# 02-MCU.net
KiCad netlist of a schematic drawn in Altium Designer
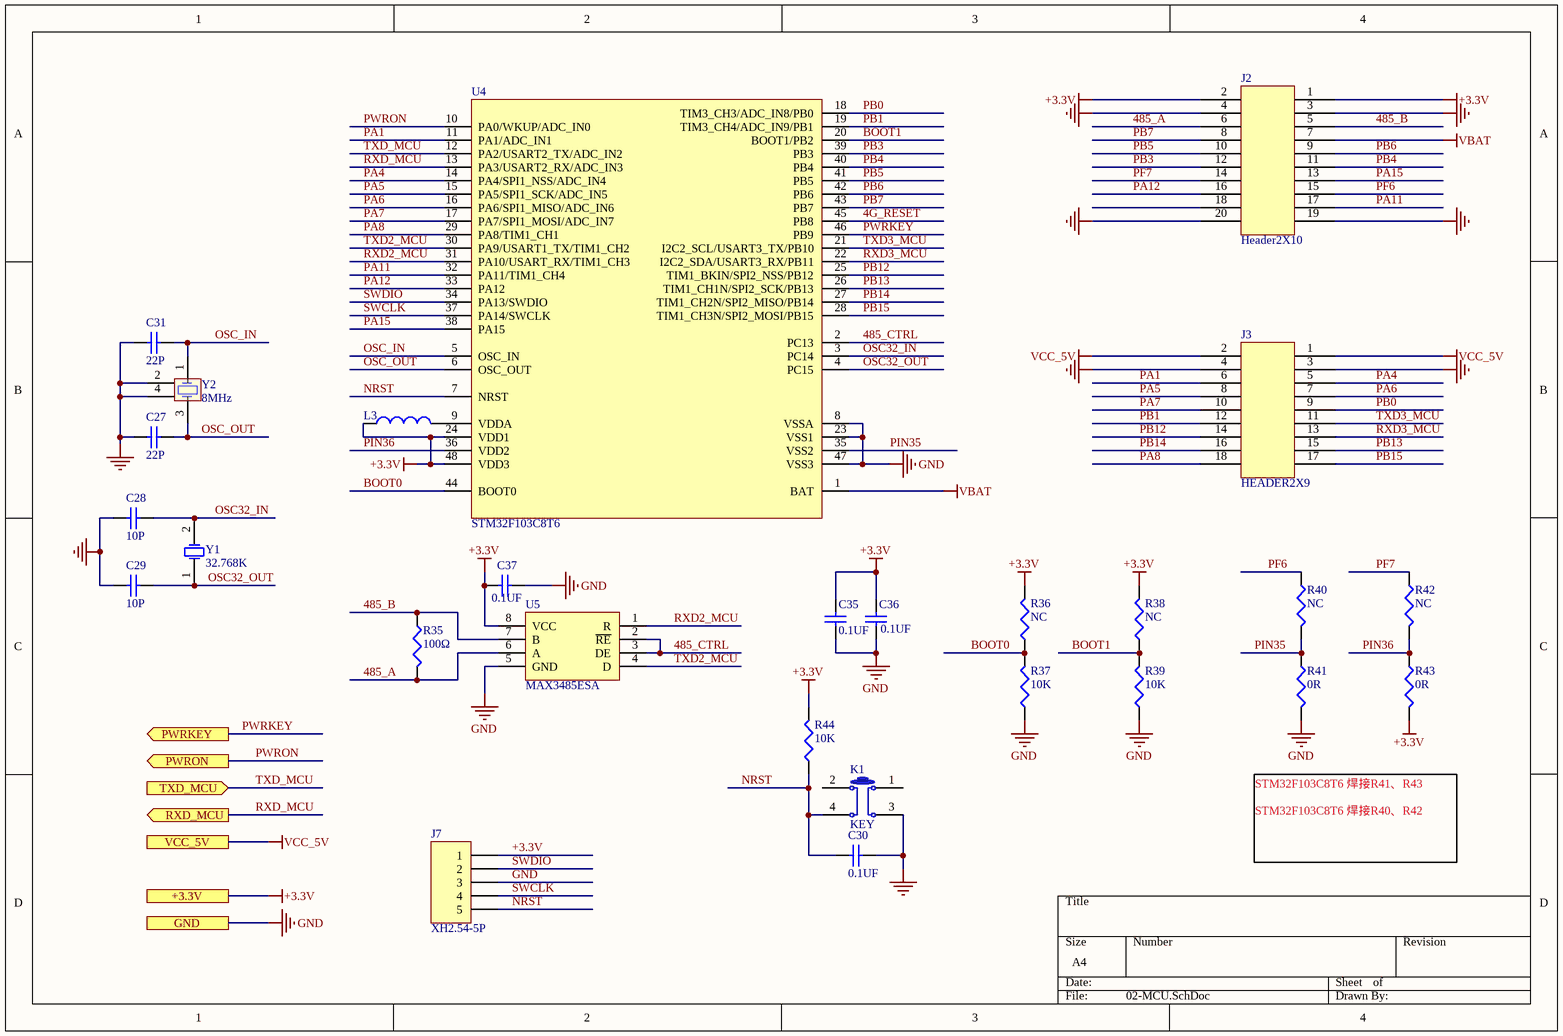
[diagram p0: 02-MCU.SchDoc]

(export (version "E")
  (design (tool "Eeschema 10.0.6"))
  (components
    (comp (ref "C27")
      (value "22P")
      (footprint "0603_C")
      (description "Capacitor")
      (fields (field (name "Comment") "Cap") (field (name "PUBLISHER") "Altium Limited"))
      (libsource (lib "Miscellaneous Devices") (part "Cap"))
    )
    (comp (ref "C28")
      (value "10P")
      (footprint "0603_C")
      (description "Capacitor")
      (fields (field (name "Comment") "Cap") (field (name "PUBLISHER") "Altium Limited"))
      (libsource (lib "Miscellaneous Devices") (part "Cap"))
    )
    (comp (ref "C29")
      (value "10P")
      (footprint "0603_C")
      (description "Capacitor")
      (fields (field (name "Comment") "Cap") (field (name "PUBLISHER") "Altium Limited"))
      (libsource (lib "Miscellaneous Devices") (part "Cap"))
    )
    (comp (ref "C30")
      (value "0.1UF")
      (footprint "0603_C")
      (description "Capacitor")
      (fields (field (name "Comment") "Cap") (field (name "PUBLISHER") "Altium Limited"))
      (libsource (lib "Miscellaneous Devices") (part "Cap"))
    )
    (comp (ref "C31")
      (value "22P")
      (footprint "0603_C")
      (description "Capacitor")
      (fields (field (name "Comment") "Cap") (field (name "PUBLISHER") "Altium Limited"))
      (libsource (lib "Miscellaneous Devices") (part "Cap"))
    )
    (comp (ref "C35")
      (value "0.1UF")
      (footprint "0603_C")
      (description "Capacitor")
      (fields (field (name "Comment") "Cap") (field (name "PUBLISHER") "Altium Limited"))
      (libsource (lib "Miscellaneous Devices") (part "Cap"))
    )
    (comp (ref "C36")
      (value "0.1UF")
      (footprint "0603_C")
      (description "Capacitor")
      (fields (field (name "Comment") "Cap") (field (name "PUBLISHER") "Altium Limited"))
      (libsource (lib "Miscellaneous Devices") (part "Cap"))
    )
    (comp (ref "C37")
      (value "0.1UF")
      (footprint "0603_C")
      (description "Capacitor")
      (fields (field (name "Comment") "Cap") (field (name "PUBLISHER") "Altium Limited"))
      (libsource (lib "Miscellaneous Devices") (part "Cap"))
    )
    (comp (ref "J2")
      (value "Header2X10")
      (footprint "DIP20-2.54-2.54")
      (libsource (lib "MySchlib") (part "Header2X10"))
    )
    (comp (ref "J3")
      (value "HEADER2X9")
      (footprint "DIP18-2.54-2.54")
      (libsource (lib "MySchlib") (part "HEADER2X9"))
    )
    (comp (ref "J7")
      (value "XH2.54-5P")
      (footprint "SIP5")
      (description "Header, 5-Pin, Right Angle")
      (fields (field (name "PUBLISHER") "Altium Limited"))
      (libsource (lib "Miscellaneous Connectors") (part "Header 5H"))
    )
    (comp (ref "K1") (value "KEY") (footprint "KEY_SMD5465") (libsource (lib "Schlib1") (part "KEY")))
    (comp (ref "L3")
      (value "Inductor")
      (footprint "0603_R")
      (fields (field (name "PUBLISHER") "Altium Limited"))
      (libsource (lib "Miscellaneous Devices") (part "Inductor"))
    )
    (comp (ref "R35") (value "100Ω") (footprint "0603_R") (libsource (lib "MySchlib") (part "RES1")))
    (comp (ref "R36")
      (value "NC")
      (footprint "0603_R")
      (description "Resistor")
      (fields (field (name "Comment") "Res3") (field (name "PUBLISHER") "Altium Limited"))
      (libsource (lib "Miscellaneous Devices") (part "Res3"))
    )
    (comp (ref "R37")
      (value "10K")
      (footprint "0603_R")
      (description "Resistor")
      (fields (field (name "Comment") "Res3") (field (name "PUBLISHER") "Altium Limited"))
      (libsource (lib "Miscellaneous Devices") (part "Res3"))
    )
    (comp (ref "R38")
      (value "NC")
      (footprint "0603_R")
      (description "Resistor")
      (fields (field (name "Comment") "Res3") (field (name "PUBLISHER") "Altium Limited"))
      (libsource (lib "Miscellaneous Devices") (part "Res3"))
    )
    (comp (ref "R39")
      (value "10K")
      (footprint "0603_R")
      (description "Resistor")
      (fields (field (name "Comment") "Res3") (field (name "PUBLISHER") "Altium Limited"))
      (libsource (lib "Miscellaneous Devices") (part "Res3"))
    )
    (comp (ref "R40")
      (value "NC")
      (footprint "0603_R")
      (description "Resistor")
      (fields (field (name "Comment") "Res3") (field (name "PUBLISHER") "Altium Limited"))
      (libsource (lib "Miscellaneous Devices") (part "Res3"))
    )
    (comp (ref "R41")
      (value "0R")
      (footprint "0603_R")
      (description "Resistor")
      (fields (field (name "Comment") "Res3") (field (name "PUBLISHER") "Altium Limited"))
      (libsource (lib "Miscellaneous Devices") (part "Res3"))
    )
    (comp (ref "R42")
      (value "NC")
      (footprint "0603_R")
      (description "Resistor")
      (fields (field (name "Comment") "Res3") (field (name "PUBLISHER") "Altium Limited"))
      (libsource (lib "Miscellaneous Devices") (part "Res3"))
    )
    (comp (ref "R43")
      (value "0R")
      (footprint "0603_R")
      (description "Resistor")
      (fields (field (name "Comment") "Res3") (field (name "PUBLISHER") "Altium Limited"))
      (libsource (lib "Miscellaneous Devices") (part "Res3"))
    )
    (comp (ref "R44")
      (value "10K")
      (footprint "0603_R")
      (description "Resistor")
      (fields (field (name "Comment") "Res3") (field (name "PUBLISHER") "Altium Limited"))
      (libsource (lib "Miscellaneous Devices") (part "Res3"))
    )
    (comp (ref "U4")
      (value "STM32F103C8T6")
      (footprint "LQFP48")
      (libsource (lib "MySchlib") (part "STM32F103C8T6"))
    )
    (comp (ref "U5") (value "MAX3485ESA") (footprint "SO8") (libsource (lib "MySchlib") (part "MAX485")))
    (comp (ref "Y1")
      (value "32.768K")
      (footprint "3215")
      (description "Crystal Oscillator")
      (fields (field (name "PUBLISHER") "Altium Limited"))
      (libsource (lib "Miscellaneous Devices") (part "XTAL"))
    )
    (comp (ref "Y2")
      (value "8MHz")
      (footprint "CRY_S3225")
      (description "CRYSTAL_S4_PASSIVE")
      (libsource (lib "EP_MCB_V4.1") (part "CRYSTAL_S4_1"))
    )
  )
  (nets
    (net (code "1") (name "+3.3V") (class "Default")
      (node (ref "C35") (pin "1") (pinfunction "1_1") (pintype "passive"))
      (node (ref "C36") (pin "1") (pinfunction "1_1") (pintype "passive"))
      (node (ref "C37") (pin "1") (pinfunction "1_1") (pintype "passive"))
      (node (ref "J2") (pin "1") (pinfunction "1_1") (pintype "passive"))
      (node (ref "J2") (pin "2") (pinfunction "2_2") (pintype "passive"))
      (node (ref "J7") (pin "1") (pinfunction "1_1") (pintype "passive"))
      (node (ref "L3") (pin "1") (pinfunction "1_1") (pintype "passive"))
      (node (ref "R36") (pin "2") (pinfunction "2_2") (pintype "passive"))
      (node (ref "R38") (pin "2") (pinfunction "2_2") (pintype "passive"))
      (node (ref "R43") (pin "2") (pinfunction "2_2") (pintype "passive"))
      (node (ref "R44") (pin "2") (pinfunction "2_2") (pintype "passive"))
      (node (ref "U4") (pin "24") (pinfunction "VDD1_24") (pintype "passive"))
      (node (ref "U4") (pin "48") (pinfunction "VDD3_48") (pintype "passive"))
      (node (ref "U5") (pin "8") (pinfunction "VCC_8") (pintype "passive"))
    )
    (net (code "2") (name "/4G_RESET") (class "Default")
      (node (ref "U4") (pin "45") (pinfunction "PB8_45") (pintype "passive"))
    )
    (net (code "3") (name "/485_A") (class "Default")
      (node (ref "J2") (pin "6") (pinfunction "6_6") (pintype "passive"))
      (node (ref "R35") (pin "2") (pinfunction "2_2") (pintype "passive"))
      (node (ref "U5") (pin "6") (pinfunction "A_6") (pintype "passive"))
    )
    (net (code "4") (name "/485_B") (class "Default")
      (node (ref "J2") (pin "5") (pinfunction "5_5") (pintype "passive"))
      (node (ref "R35") (pin "1") (pinfunction "1_1") (pintype "passive"))
      (node (ref "U5") (pin "7") (pinfunction "B_7") (pintype "passive"))
    )
    (net (code "5") (name "/485_CTRL") (class "Default")
      (node (ref "U4") (pin "2") (pinfunction "PC13_2") (pintype "passive"))
      (node (ref "U5") (pin "2") (pinfunction "~{RE}_2") (pintype "passive"))
      (node (ref "U5") (pin "3") (pinfunction "DE_3") (pintype "passive"))
    )
    (net (code "6") (name "/BOOT0") (class "Default")
      (node (ref "R36") (pin "1") (pinfunction "1_1") (pintype "passive"))
      (node (ref "R37") (pin "2") (pinfunction "2_2") (pintype "passive"))
      (node (ref "U4") (pin "44") (pinfunction "BOOT0_44") (pintype "passive"))
    )
    (net (code "7") (name "/BOOT1") (class "Default")
      (node (ref "R38") (pin "1") (pinfunction "1_1") (pintype "passive"))
      (node (ref "R39") (pin "2") (pinfunction "2_2") (pintype "passive"))
      (node (ref "U4") (pin "20") (pinfunction "BOOT1/PB2_20") (pintype "passive"))
    )
    (net (code "8") (name "/NRST") (class "Default")
      (node (ref "C30") (pin "2") (pinfunction "2_2") (pintype "passive"))
      (node (ref "J7") (pin "5") (pinfunction "5_5") (pintype "passive"))
      (node (ref "K1") (pin "4") (pinfunction "4_4") (pintype "passive"))
      (node (ref "R44") (pin "1") (pinfunction "1_1") (pintype "passive"))
      (node (ref "U4") (pin "7") (pinfunction "NRST_7") (pintype "passive"))
    )
    (net (code "9") (name "/OSC32_IN") (class "Default")
      (node (ref "C28") (pin "1") (pinfunction "1_1") (pintype "passive"))
      (node (ref "U4") (pin "3") (pinfunction "PC14_3") (pintype "passive"))
      (node (ref "Y1") (pin "2") (pinfunction "OSC2_2") (pintype "passive"))
    )
    (net (code "10") (name "/OSC32_OUT") (class "Default")
      (node (ref "C29") (pin "1") (pinfunction "1_1") (pintype "passive"))
      (node (ref "U4") (pin "4") (pinfunction "PC15_4") (pintype "passive"))
      (node (ref "Y1") (pin "1") (pinfunction "OSC1_1") (pintype "passive"))
    )
    (net (code "11") (name "/OSC_IN") (class "Default")
      (node (ref "C31") (pin "1") (pinfunction "1_1") (pintype "passive"))
      (node (ref "U4") (pin "5") (pinfunction "OSC_IN_5") (pintype "passive"))
      (node (ref "Y2") (pin "1") (pinfunction "1_1") (pintype "passive"))
    )
    (net (code "12") (name "/OSC_OUT") (class "Default")
      (node (ref "C27") (pin "1") (pinfunction "1_1") (pintype "passive"))
      (node (ref "U4") (pin "6") (pinfunction "OSC_OUT_6") (pintype "passive"))
      (node (ref "Y2") (pin "3") (pinfunction "3_3") (pintype "passive"))
    )
    (net (code "13") (name "/PA1") (class "Default")
      (node (ref "J3") (pin "6") (pinfunction "6_6") (pintype "passive"))
      (node (ref "U4") (pin "11") (pinfunction "PA1/ADC_IN1_11") (pintype "passive"))
    )
    (net (code "14") (name "/PA4") (class "Default")
      (node (ref "J3") (pin "5") (pinfunction "5_5") (pintype "passive"))
      (node (ref "U4") (pin "14") (pinfunction "PA4/SPI1_NSS/ADC_IN4_14") (pintype "passive"))
    )
    (net (code "15") (name "/PA5") (class "Default")
      (node (ref "J3") (pin "8") (pinfunction "8_8") (pintype "passive"))
      (node (ref "U4") (pin "15") (pinfunction "PA5/SPI1_SCK/ADC_IN5_15") (pintype "passive"))
    )
    (net (code "16") (name "/PA6") (class "Default")
      (node (ref "J3") (pin "7") (pinfunction "7_7") (pintype "passive"))
      (node (ref "U4") (pin "16") (pinfunction "PA6/SPI1_MISO/ADC_IN6_16") (pintype "passive"))
    )
    (net (code "17") (name "/PA7") (class "Default")
      (node (ref "J3") (pin "10") (pinfunction "10_10") (pintype "passive"))
      (node (ref "U4") (pin "17") (pinfunction "PA7/SPI1_MOSI/ADC_IN7_17") (pintype "passive"))
    )
    (net (code "18") (name "/PA8") (class "Default")
      (node (ref "J3") (pin "18") (pinfunction "18_18") (pintype "passive"))
      (node (ref "U4") (pin "29") (pinfunction "PA8/TIM1_CH1_29") (pintype "passive"))
    )
    (net (code "19") (name "/PA11") (class "Default")
      (node (ref "J2") (pin "17") (pinfunction "17_17") (pintype "passive"))
      (node (ref "U4") (pin "32") (pinfunction "PA11/TIM1_CH4_32") (pintype "passive"))
    )
    (net (code "20") (name "/PA12") (class "Default")
      (node (ref "J2") (pin "16") (pinfunction "16_16") (pintype "passive"))
      (node (ref "U4") (pin "33") (pinfunction "PA12_33") (pintype "passive"))
    )
    (net (code "21") (name "/PA15") (class "Default")
      (node (ref "J2") (pin "13") (pinfunction "13_13") (pintype "passive"))
      (node (ref "U4") (pin "38") (pinfunction "PA15_38") (pintype "passive"))
    )
    (net (code "22") (name "/PB0") (class "Default")
      (node (ref "J3") (pin "9") (pinfunction "9_9") (pintype "passive"))
      (node (ref "U4") (pin "18") (pinfunction "TIM3_CH3/ADC_IN8/PB0_18") (pintype "passive"))
    )
    (net (code "23") (name "/PB1") (class "Default")
      (node (ref "J3") (pin "12") (pinfunction "12_12") (pintype "passive"))
      (node (ref "U4") (pin "19") (pinfunction "TIM3_CH4/ADC_IN9/PB1_19") (pintype "passive"))
    )
    (net (code "24") (name "/PB3") (class "Default")
      (node (ref "J2") (pin "12") (pinfunction "12_12") (pintype "passive"))
      (node (ref "U4") (pin "39") (pinfunction "PB3_39") (pintype "passive"))
    )
    (net (code "25") (name "/PB4") (class "Default")
      (node (ref "J2") (pin "11") (pinfunction "11_11") (pintype "passive"))
      (node (ref "U4") (pin "40") (pinfunction "PB4_40") (pintype "passive"))
    )
    (net (code "26") (name "/PB5") (class "Default")
      (node (ref "J2") (pin "10") (pinfunction "10_10") (pintype "passive"))
      (node (ref "U4") (pin "41") (pinfunction "PB5_41") (pintype "passive"))
    )
    (net (code "27") (name "/PB6") (class "Default")
      (node (ref "J2") (pin "9") (pinfunction "9_9") (pintype "passive"))
      (node (ref "U4") (pin "42") (pinfunction "PB6_42") (pintype "passive"))
    )
    (net (code "28") (name "/PB7") (class "Default")
      (node (ref "J2") (pin "8") (pinfunction "8_8") (pintype "passive"))
      (node (ref "U4") (pin "43") (pinfunction "PB7_43") (pintype "passive"))
    )
    (net (code "29") (name "/PB12") (class "Default")
      (node (ref "J3") (pin "14") (pinfunction "14_14") (pintype "passive"))
      (node (ref "U4") (pin "25") (pinfunction "TIM1_BKIN/SPI2_NSS/PB12_25") (pintype "passive"))
    )
    (net (code "30") (name "/PB13") (class "Default")
      (node (ref "J3") (pin "15") (pinfunction "15_15") (pintype "passive"))
      (node (ref "U4") (pin "26") (pinfunction "TIM1_CH1N/SPI2_SCK/PB13_26") (pintype "passive"))
    )
    (net (code "31") (name "/PB14") (class "Default")
      (node (ref "J3") (pin "16") (pinfunction "16_16") (pintype "passive"))
      (node (ref "U4") (pin "27") (pinfunction "TIM1_CH2N/SPI2_MISO/PB14_27") (pintype "passive"))
    )
    (net (code "32") (name "/PB15") (class "Default")
      (node (ref "J3") (pin "17") (pinfunction "17_17") (pintype "passive"))
      (node (ref "U4") (pin "28") (pinfunction "TIM1_CH3N/SPI2_MOSI/PB15_28") (pintype "passive"))
    )
    (net (code "33") (name "/PF6") (class "Default")
      (node (ref "J2") (pin "15") (pinfunction "15_15") (pintype "passive"))
      (node (ref "R40") (pin "1") (pinfunction "1_1") (pintype "passive"))
    )
    (net (code "34") (name "/PF7") (class "Default")
      (node (ref "J2") (pin "14") (pinfunction "14_14") (pintype "passive"))
      (node (ref "R42") (pin "1") (pinfunction "1_1") (pintype "passive"))
    )
    (net (code "35") (name "/PIN35") (class "Default")
      (node (ref "R40") (pin "2") (pinfunction "2_2") (pintype "passive"))
      (node (ref "R41") (pin "1") (pinfunction "1_1") (pintype "passive"))
      (node (ref "U4") (pin "35") (pinfunction "VSS2_35") (pintype "passive"))
    )
    (net (code "36") (name "/PIN36") (class "Default")
      (node (ref "R42") (pin "2") (pinfunction "2_2") (pintype "passive"))
      (node (ref "R43") (pin "1") (pinfunction "1_1") (pintype "passive"))
      (node (ref "U4") (pin "36") (pinfunction "VDD2_36") (pintype "passive"))
    )
    (net (code "37") (name "/PWRKEY") (class "Default")
      (node (ref "U4") (pin "46") (pinfunction "PB9_46") (pintype "passive"))
    )
    (net (code "38") (name "/PWRON") (class "Default")
      (node (ref "U4") (pin "10") (pinfunction "PA0/WKUP/ADC_IN0_10") (pintype "passive"))
    )
    (net (code "39") (name "/RXD2_MCU") (class "Default")
      (node (ref "U4") (pin "31") (pinfunction "PA10/USART_RX/TIM1_CH3_31") (pintype "passive"))
      (node (ref "U5") (pin "1") (pinfunction "R_1") (pintype "passive"))
    )
    (net (code "40") (name "/RXD3_MCU") (class "Default")
      (node (ref "J3") (pin "13") (pinfunction "13_13") (pintype "passive"))
      (node (ref "U4") (pin "22") (pinfunction "I2C2_SDA/USART3_RX/PB11_22") (pintype "passive"))
    )
    (net (code "41") (name "/RXD_MCU") (class "Default")
      (node (ref "U4") (pin "13") (pinfunction "PA3/USART2_RX/ADC_IN3_13") (pintype "passive"))
    )
    (net (code "42") (name "/SWCLK") (class "Default")
      (node (ref "J7") (pin "4") (pinfunction "4_4") (pintype "passive"))
      (node (ref "U4") (pin "37") (pinfunction "PA14/SWCLK_37") (pintype "passive"))
    )
    (net (code "43") (name "/SWDIO") (class "Default")
      (node (ref "J7") (pin "2") (pinfunction "2_2") (pintype "passive"))
      (node (ref "U4") (pin "34") (pinfunction "PA13/SWDIO_34") (pintype "passive"))
    )
    (net (code "44") (name "/TXD2_MCU") (class "Default")
      (node (ref "U4") (pin "30") (pinfunction "PA9/USART1_TX/TIM1_CH2_30") (pintype "passive"))
      (node (ref "U5") (pin "4") (pinfunction "D_4") (pintype "passive"))
    )
    (net (code "45") (name "/TXD3_MCU") (class "Default")
      (node (ref "J3") (pin "11") (pinfunction "11_11") (pintype "passive"))
      (node (ref "U4") (pin "21") (pinfunction "I2C2_SCL/USART3_TX/PB10_21") (pintype "passive"))
    )
    (net (code "46") (name "/TXD_MCU") (class "Default")
      (node (ref "U4") (pin "12") (pinfunction "PA2/USART2_TX/ADC_IN2_12") (pintype "passive"))
    )
    (net (code "47") (name "GND") (class "Default")
      (node (ref "C27") (pin "2") (pinfunction "2_2") (pintype "passive"))
      (node (ref "C28") (pin "2") (pinfunction "2_2") (pintype "passive"))
      (node (ref "C29") (pin "2") (pinfunction "2_2") (pintype "passive"))
      (node (ref "C30") (pin "1") (pinfunction "1_1") (pintype "passive"))
      (node (ref "C31") (pin "2") (pinfunction "2_2") (pintype "passive"))
      (node (ref "C35") (pin "2") (pinfunction "2_2") (pintype "passive"))
      (node (ref "C36") (pin "2") (pinfunction "2_2") (pintype "passive"))
      (node (ref "C37") (pin "2") (pinfunction "2_2") (pintype "passive"))
      (node (ref "J2") (pin "19") (pinfunction "19_19") (pintype "passive"))
      (node (ref "J2") (pin "20") (pinfunction "20_20") (pintype "passive"))
      (node (ref "J2") (pin "3") (pinfunction "3_3") (pintype "passive"))
      (node (ref "J2") (pin "4") (pinfunction "4_4") (pintype "passive"))
      (node (ref "J3") (pin "3") (pinfunction "3_3") (pintype "passive"))
      (node (ref "J3") (pin "4") (pinfunction "4_4") (pintype "passive"))
      (node (ref "J7") (pin "3") (pinfunction "3_3") (pintype "passive"))
      (node (ref "K1") (pin "3") (pinfunction "3_3") (pintype "passive"))
      (node (ref "R37") (pin "1") (pinfunction "1_1") (pintype "passive"))
      (node (ref "R39") (pin "1") (pinfunction "1_1") (pintype "passive"))
      (node (ref "R41") (pin "2") (pinfunction "2_2") (pintype "passive"))
      (node (ref "U4") (pin "23") (pinfunction "VSS1_23") (pintype "passive"))
      (node (ref "U4") (pin "47") (pinfunction "VSS3_47") (pintype "passive"))
      (node (ref "U4") (pin "8") (pinfunction "VSSA_8") (pintype "passive"))
      (node (ref "U5") (pin "5") (pinfunction "GND_5") (pintype "passive"))
      (node (ref "Y2") (pin "2") (pinfunction "2_2") (pintype "passive"))
      (node (ref "Y2") (pin "4") (pinfunction "4_4") (pintype "passive"))
    )
    (net (code "48") (name "Net-(U4-VDDA)") (class "Default")
      (node (ref "L3") (pin "2") (pinfunction "2_2") (pintype "passive"))
      (node (ref "U4") (pin "9") (pinfunction "VDDA_9") (pintype "passive"))
    )
    (net (code "49") (name "VBAT") (class "Default")
      (node (ref "J2") (pin "7") (pinfunction "7_7") (pintype "passive"))
      (node (ref "U4") (pin "1") (pinfunction "BAT_1") (pintype "passive"))
    )
    (net (code "50") (name "VCC_5V") (class "Default")
      (node (ref "J3") (pin "1") (pinfunction "1_1") (pintype "passive"))
      (node (ref "J3") (pin "2") (pinfunction "2_2") (pintype "passive"))
    )
    (net (code "51") (name "unconnected-(J2-Pad18)") (class "Default")
      (node (ref "J2") (pin "18") (pinfunction "18_18") (pintype "passive"))
    )
    (net (code "52") (name "unconnected-(K1-Pad1)") (class "Default")
      (node (ref "K1") (pin "1") (pinfunction "1_1") (pintype "passive"))
    )
    (net (code "53") (name "unconnected-(K1-Pad2)") (class "Default")
      (node (ref "K1") (pin "2") (pinfunction "2_2") (pintype "passive"))
    )
  )
)
